# Rechargeable_battery_capacity_tester_v1a.net
KiCad netlist of a schematic drawn in EAGLE
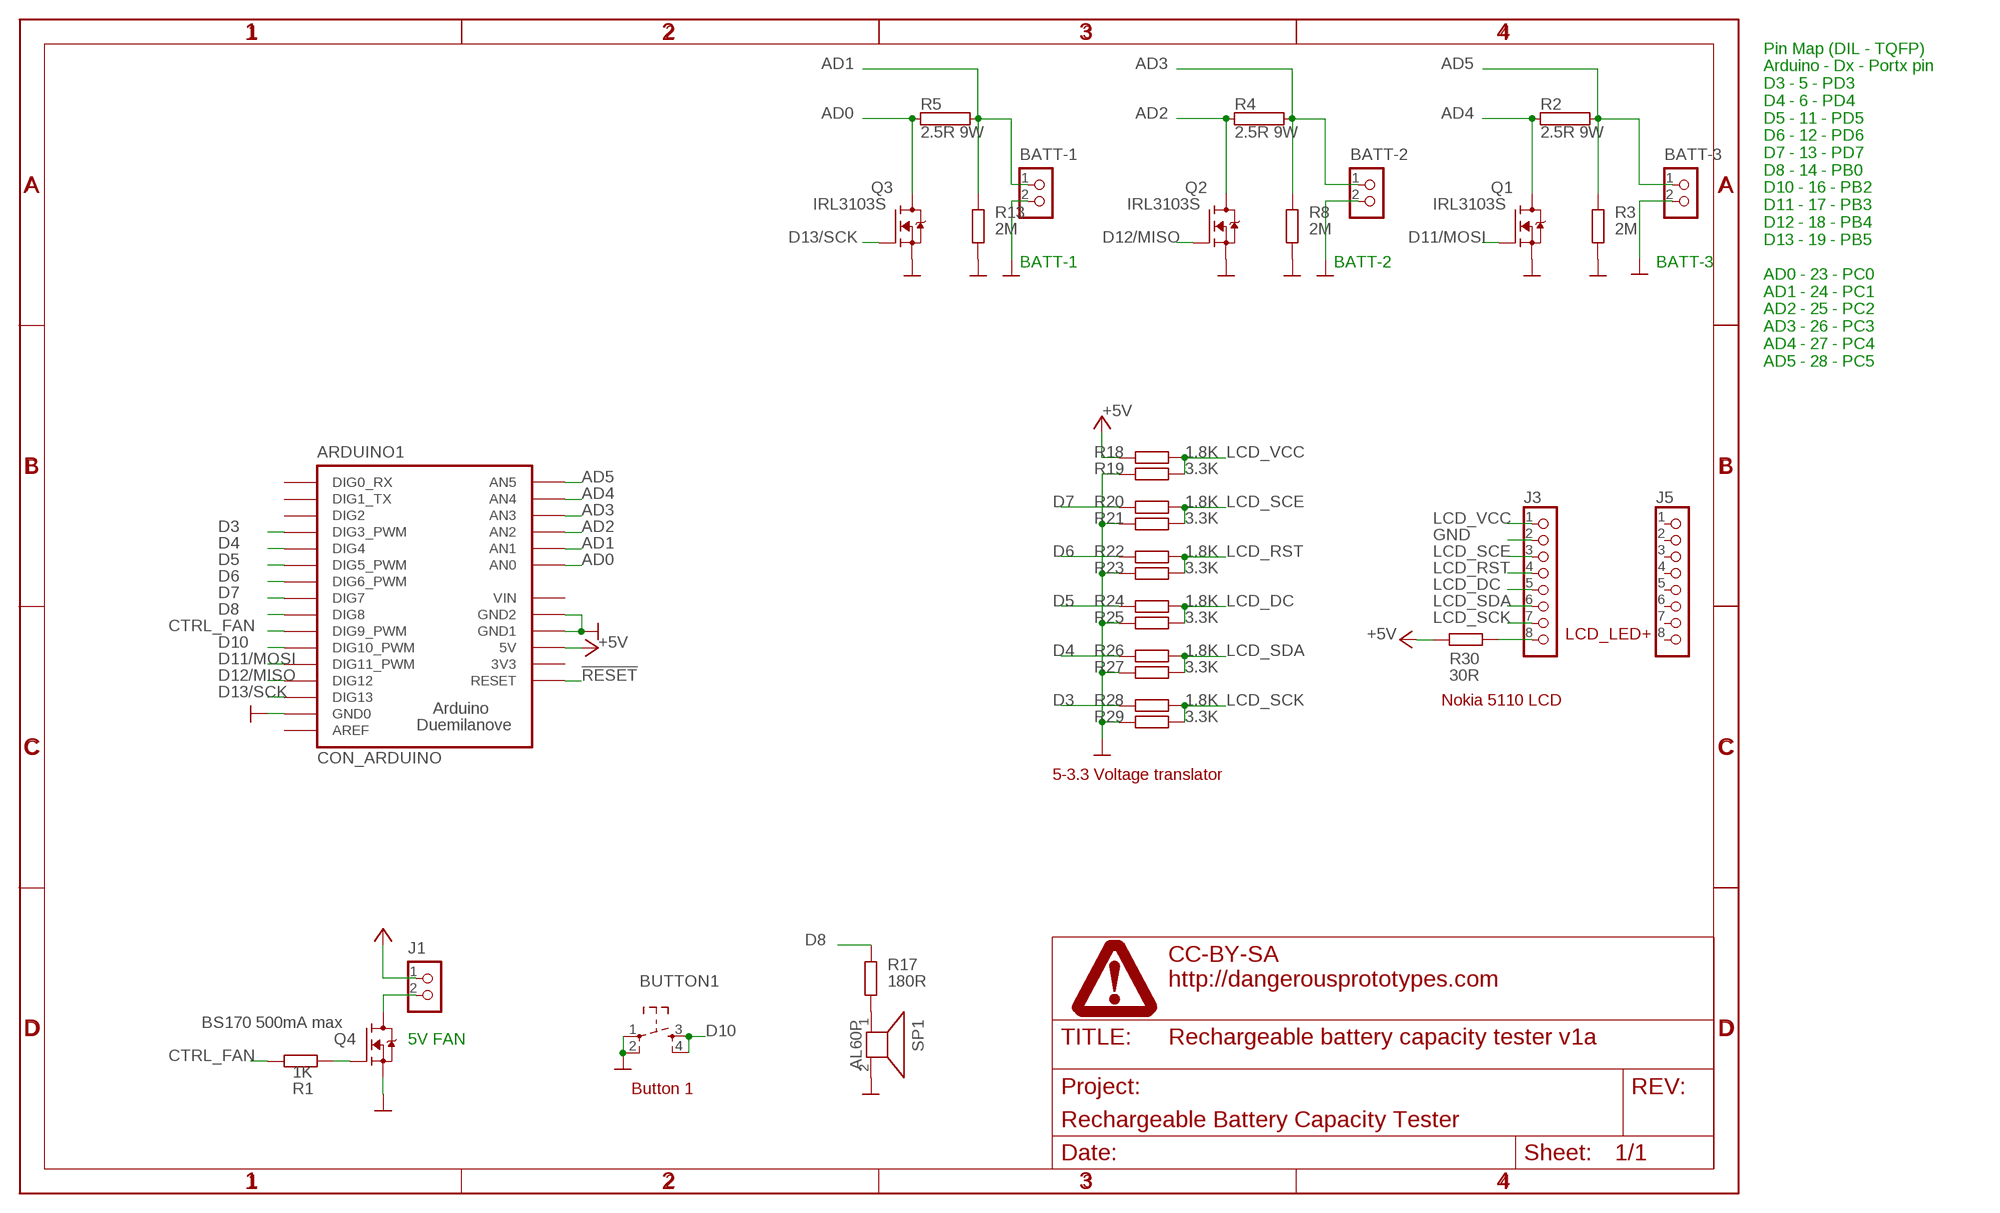
[diagram p0: schematic, sheet 1]

(export (version "E")
  (design (tool "Eeschema 10.0.6"))
  (components
    (comp (ref "ARDUINO1")
      (value "CON_ARDUINO")
      (footprint "eagle-import:CON_ARDUINO")
      (libsource (lib "eagle-import") (part "CON_ARDUINO"))
    )
    (comp (ref "BATT-1")
      (value "CON_TERMINAL_BLOCK_02-5MM")
      (footprint "eagle-import:TERMINAL_BLOCK_2P_5")
      (libsource (lib "eagle-import") (part "CON_TERMINAL_BLOCK_02-5MM"))
    )
    (comp (ref "BATT-2")
      (value "CON_TERMINAL_BLOCK_02-5MM")
      (footprint "eagle-import:TERMINAL_BLOCK_2P_5")
      (libsource (lib "eagle-import") (part "CON_TERMINAL_BLOCK_02-5MM"))
    )
    (comp (ref "BATT-3")
      (value "CON_TERMINAL_BLOCK_02-5MM")
      (footprint "eagle-import:TERMINAL_BLOCK_2P_5")
      (libsource (lib "eagle-import") (part "CON_TERMINAL_BLOCK_02-5MM"))
    )
    (comp (ref "BUTTON1")
      (value "SW_TACT_4P")
      (footprint "eagle-import:SW_TACT_SMALL")
      (libsource (lib "eagle-import") (part "SW_TACT_4P"))
    )
    (comp (ref "J1")
      (value "CON_JST_2PIN-PTH")
      (footprint "eagle-import:CON_JST_2PIN")
      (libsource (lib "eagle-import") (part "CON_JST_2PIN-PTH"))
    )
    (comp (ref "J3")
      (value "CON_HEADER_1X08-PTH")
      (footprint "eagle-import:M1X8")
      (libsource (lib "eagle-import") (part "CON_HEADER_1X08-PTH"))
    )
    (comp (ref "J5")
      (value "CON_HEADER_1X08-PTH")
      (footprint "eagle-import:M1X8")
      (libsource (lib "eagle-import") (part "CON_HEADER_1X08-PTH"))
    )
    (comp (ref "Q1")
      (value "IRL3103S")
      (footprint "eagle-import:D2PAK")
      (libsource (lib "eagle-import") (part "TRANSISTOR_MOSFET-N-D2PAK"))
    )
    (comp (ref "Q2")
      (value "IRL3103S")
      (footprint "eagle-import:D2PAK")
      (libsource (lib "eagle-import") (part "TRANSISTOR_MOSFET-N-D2PAK"))
    )
    (comp (ref "Q3")
      (value "IRL3103S")
      (footprint "eagle-import:D2PAK")
      (libsource (lib "eagle-import") (part "TRANSISTOR_MOSFET-N-D2PAK"))
    )
    (comp (ref "Q4")
      (value "BS170 500mA max")
      (footprint "eagle-import:SOT-23")
      (libsource (lib "eagle-import") (part "TRANSISTOR_FET_BS170-SOT-23"))
    )
    (comp (ref "R1")
      (value "1K")
      (footprint "eagle-import:R603")
      (libsource (lib "eagle-import") (part "RESISTOR-0603"))
    )
    (comp (ref "R2")
      (value "2.5R 9W")
      (footprint "eagle-import:KH214-8")
      (libsource (lib "eagle-import") (part "RKH214-8"))
    )
    (comp (ref "R3")
      (value "2M")
      (footprint "eagle-import:R603")
      (libsource (lib "eagle-import") (part "RESISTOR-0603"))
    )
    (comp (ref "R4")
      (value "2.5R 9W")
      (footprint "eagle-import:KH214-8")
      (libsource (lib "eagle-import") (part "RKH214-8"))
    )
    (comp (ref "R5")
      (value "2.5R 9W")
      (footprint "eagle-import:KH214-8")
      (libsource (lib "eagle-import") (part "RKH214-8"))
    )
    (comp (ref "R8")
      (value "2M")
      (footprint "eagle-import:R603")
      (libsource (lib "eagle-import") (part "RESISTOR-0603"))
    )
    (comp (ref "R13")
      (value "2M")
      (footprint "eagle-import:R603")
      (libsource (lib "eagle-import") (part "RESISTOR-0603"))
    )
    (comp (ref "R17")
      (value "180R")
      (footprint "eagle-import:R603")
      (libsource (lib "eagle-import") (part "RESISTOR-0603"))
    )
    (comp (ref "R18")
      (value "1.8K")
      (footprint "eagle-import:R603")
      (libsource (lib "eagle-import") (part "RESISTOR-0603"))
    )
    (comp (ref "R19")
      (value "3.3K")
      (footprint "eagle-import:R603")
      (libsource (lib "eagle-import") (part "RESISTOR-0603"))
    )
    (comp (ref "R20")
      (value "1.8K")
      (footprint "eagle-import:R603")
      (libsource (lib "eagle-import") (part "RESISTOR-0603"))
    )
    (comp (ref "R21")
      (value "3.3K")
      (footprint "eagle-import:R603")
      (libsource (lib "eagle-import") (part "RESISTOR-0603"))
    )
    (comp (ref "R22")
      (value "1.8K")
      (footprint "eagle-import:R603")
      (libsource (lib "eagle-import") (part "RESISTOR-0603"))
    )
    (comp (ref "R23")
      (value "3.3K")
      (footprint "eagle-import:R603")
      (libsource (lib "eagle-import") (part "RESISTOR-0603"))
    )
    (comp (ref "R24")
      (value "1.8K")
      (footprint "eagle-import:R603")
      (libsource (lib "eagle-import") (part "RESISTOR-0603"))
    )
    (comp (ref "R25")
      (value "3.3K")
      (footprint "eagle-import:R603")
      (libsource (lib "eagle-import") (part "RESISTOR-0603"))
    )
    (comp (ref "R26")
      (value "1.8K")
      (footprint "eagle-import:R603")
      (libsource (lib "eagle-import") (part "RESISTOR-0603"))
    )
    (comp (ref "R27")
      (value "3.3K")
      (footprint "eagle-import:R603")
      (libsource (lib "eagle-import") (part "RESISTOR-0603"))
    )
    (comp (ref "R28")
      (value "1.8K")
      (footprint "eagle-import:R603")
      (libsource (lib "eagle-import") (part "RESISTOR-0603"))
    )
    (comp (ref "R29")
      (value "3.3K")
      (footprint "eagle-import:R603")
      (libsource (lib "eagle-import") (part "RESISTOR-0603"))
    )
    (comp (ref "R30")
      (value "30R")
      (footprint "eagle-import:R603")
      (libsource (lib "eagle-import") (part "RESISTOR-0603"))
    )
    (comp (ref "SP1")
      (value "AL60P")
      (footprint "eagle-import:AL60P")
      (libsource (lib "eagle-import") (part "AL60P"))
    )
    (comp (ref "U$1")
      (value "FRAME_DINA4_L")
      (footprint "eagle-import:DP_LOGO")
      (fields
        (field (name "FF1") "Credits to: http://www.instructables.com/member/BrianH/")
        (field (name "PROJECT") "Rechargeable Battery Capacity Tester")
        (field (name "URL1") "http://dangerousprototypes.com")
        (field (name "URL2") "http://www.instructables.com/id/Rechargeable-Battery-Capacity-Tester/")
      )
      (libsource (lib "eagle-import") (part "FRAME_DINA4_L"))
    )
  )
  (nets
    (net (code "1") (name "/AD0") (class "Default")
      (node (ref "ARDUINO1") (pin "A_0") (pinfunction "AN0_A_0") (pintype "input"))
      (node (ref "Q3") (pin "2") (pinfunction "D_2") (pintype "passive"))
      (node (ref "R5") (pin "1") (pinfunction "1_1") (pintype "passive"))
    )
    (net (code "2") (name "/AD1") (class "Default")
      (node (ref "ARDUINO1") (pin "A_1") (pinfunction "AN1_A_1") (pintype "input"))
      (node (ref "BATT-1") (pin "1") (pinfunction "1_1") (pintype "passive"))
      (node (ref "R13") (pin "2") (pinfunction "2_2") (pintype "passive"))
      (node (ref "R5") (pin "2") (pinfunction "2_2") (pintype "passive"))
    )
    (net (code "3") (name "/AD2") (class "Default")
      (node (ref "ARDUINO1") (pin "A_2") (pinfunction "AN2_A_2") (pintype "input"))
      (node (ref "Q2") (pin "2") (pinfunction "D_2") (pintype "passive"))
      (node (ref "R4") (pin "1") (pinfunction "1_1") (pintype "passive"))
    )
    (net (code "4") (name "/AD3") (class "Default")
      (node (ref "ARDUINO1") (pin "A_3") (pinfunction "AN3_A_3") (pintype "input"))
      (node (ref "BATT-2") (pin "1") (pinfunction "1_1") (pintype "passive"))
      (node (ref "R4") (pin "2") (pinfunction "2_2") (pintype "passive"))
      (node (ref "R8") (pin "2") (pinfunction "2_2") (pintype "passive"))
    )
    (net (code "5") (name "/AD4") (class "Default")
      (node (ref "ARDUINO1") (pin "A_4") (pinfunction "AN4_A_4") (pintype "input"))
      (node (ref "Q1") (pin "2") (pinfunction "D_2") (pintype "passive"))
      (node (ref "R2") (pin "1") (pinfunction "1_1") (pintype "passive"))
    )
    (net (code "6") (name "/AD5") (class "Default")
      (node (ref "ARDUINO1") (pin "A_5") (pinfunction "AN5_A_5") (pintype "input"))
      (node (ref "BATT-3") (pin "1") (pinfunction "1_1") (pintype "passive"))
      (node (ref "R2") (pin "2") (pinfunction "2_2") (pintype "passive"))
      (node (ref "R3") (pin "2") (pinfunction "2_2") (pintype "passive"))
    )
    (net (code "7") (name "/CTRL_FAN") (class "Default")
      (node (ref "ARDUINO1") (pin "D_9") (pinfunction "DIG9_PWM_D_9") (pintype "bidirectional"))
      (node (ref "R1") (pin "1") (pinfunction "1_1") (pintype "passive"))
    )
    (net (code "8") (name "/D3") (class "Default")
      (node (ref "ARDUINO1") (pin "D_3") (pinfunction "DIG3_PWM_D_3") (pintype "bidirectional"))
      (node (ref "R28") (pin "1") (pinfunction "1_1") (pintype "passive"))
    )
    (net (code "9") (name "/D4") (class "Default")
      (node (ref "ARDUINO1") (pin "D_4") (pinfunction "DIG4_D_4") (pintype "bidirectional"))
      (node (ref "R26") (pin "1") (pinfunction "1_1") (pintype "passive"))
    )
    (net (code "10") (name "/D5") (class "Default")
      (node (ref "ARDUINO1") (pin "D_5") (pinfunction "DIG5_PWM_D_5") (pintype "bidirectional"))
      (node (ref "R24") (pin "1") (pinfunction "1_1") (pintype "passive"))
    )
    (net (code "11") (name "/D6") (class "Default")
      (node (ref "ARDUINO1") (pin "D_6") (pinfunction "DIG6_PWM_D_6") (pintype "bidirectional"))
      (node (ref "R22") (pin "1") (pinfunction "1_1") (pintype "passive"))
    )
    (net (code "12") (name "/D7") (class "Default")
      (node (ref "ARDUINO1") (pin "D_7") (pinfunction "DIG7_D_7") (pintype "bidirectional"))
      (node (ref "R20") (pin "1") (pinfunction "1_1") (pintype "passive"))
    )
    (net (code "13") (name "/D8") (class "Default")
      (node (ref "ARDUINO1") (pin "D_8") (pinfunction "DIG8_D_8") (pintype "bidirectional"))
      (node (ref "R17") (pin "2") (pinfunction "2_2") (pintype "passive"))
    )
    (net (code "14") (name "/D10") (class "Default")
      (node (ref "ARDUINO1") (pin "D_10") (pinfunction "DIG10_PWM_D_10") (pintype "bidirectional"))
      (node (ref "BUTTON1") (pin "3") (pinfunction "3_3") (pintype "passive"))
      (node (ref "BUTTON1") (pin "4") (pinfunction "4_4") (pintype "passive"))
    )
    (net (code "15") (name "/D11{slash}MOSI") (class "Default")
      (node (ref "ARDUINO1") (pin "D_11") (pinfunction "DIG11_PWM_D_11") (pintype "bidirectional"))
      (node (ref "Q1") (pin "1") (pinfunction "G_1") (pintype "passive"))
    )
    (net (code "16") (name "/D12{slash}MISO") (class "Default")
      (node (ref "ARDUINO1") (pin "D_12") (pinfunction "DIG12_D_12") (pintype "bidirectional"))
      (node (ref "Q2") (pin "1") (pinfunction "G_1") (pintype "passive"))
    )
    (net (code "17") (name "/D13{slash}SCK") (class "Default")
      (node (ref "ARDUINO1") (pin "D_13") (pinfunction "DIG13_D_13") (pintype "bidirectional"))
      (node (ref "Q3") (pin "1") (pinfunction "G_1") (pintype "passive"))
    )
    (net (code "18") (name "/LCD_DC") (class "Default")
      (node (ref "J3") (pin "5") (pinfunction "5_5") (pintype "passive"))
      (node (ref "R24") (pin "2") (pinfunction "2_2") (pintype "passive"))
      (node (ref "R25") (pin "2") (pinfunction "2_2") (pintype "passive"))
    )
    (net (code "19") (name "/LCD_RST") (class "Default")
      (node (ref "J3") (pin "4") (pinfunction "4_4") (pintype "passive"))
      (node (ref "R22") (pin "2") (pinfunction "2_2") (pintype "passive"))
      (node (ref "R23") (pin "2") (pinfunction "2_2") (pintype "passive"))
    )
    (net (code "20") (name "/LCD_SCE") (class "Default")
      (node (ref "J3") (pin "3") (pinfunction "3_3") (pintype "passive"))
      (node (ref "R20") (pin "2") (pinfunction "2_2") (pintype "passive"))
      (node (ref "R21") (pin "2") (pinfunction "2_2") (pintype "passive"))
    )
    (net (code "21") (name "/LCD_SCK") (class "Default")
      (node (ref "J3") (pin "7") (pinfunction "7_7") (pintype "passive"))
      (node (ref "R28") (pin "2") (pinfunction "2_2") (pintype "passive"))
      (node (ref "R29") (pin "2") (pinfunction "2_2") (pintype "passive"))
    )
    (net (code "22") (name "/LCD_SDA") (class "Default")
      (node (ref "J3") (pin "6") (pinfunction "6_6") (pintype "passive"))
      (node (ref "R26") (pin "2") (pinfunction "2_2") (pintype "passive"))
      (node (ref "R27") (pin "2") (pinfunction "2_2") (pintype "passive"))
    )
    (net (code "23") (name "/LCD_VCC") (class "Default")
      (node (ref "J3") (pin "1") (pinfunction "1_1") (pintype "passive"))
      (node (ref "R18") (pin "2") (pinfunction "2_2") (pintype "passive"))
      (node (ref "R19") (pin "2") (pinfunction "2_2") (pintype "passive"))
    )
    (net (code "24") (name "/VIN") (class "Default")
      (node (ref "ARDUINO1") (pin "VIN") (pinfunction "VIN_VIN") (pintype "power_in"))
    )
    (net (code "25") (name "/~{RESET}") (class "Default")
      (node (ref "ARDUINO1") (pin "RESET") (pinfunction "RESET_RESET") (pintype "input"))
    )
    (net (code "26") (name "Net-(J3-Pad8)") (class "Default")
      (node (ref "J3") (pin "8") (pinfunction "8_8") (pintype "passive"))
      (node (ref "R30") (pin "2") (pinfunction "2_2") (pintype "passive"))
    )
    (net (code "27") (name "Net-(Q4-D)") (class "Default")
      (node (ref "J1") (pin "2") (pinfunction "2_2") (pintype "passive"))
      (node (ref "Q4") (pin "3") (pinfunction "D_3") (pintype "passive"))
    )
    (net (code "28") (name "Net-(Q4-G)") (class "Default")
      (node (ref "Q4") (pin "1") (pinfunction "G_1") (pintype "passive"))
      (node (ref "R1") (pin "2") (pinfunction "2_2") (pintype "passive"))
    )
    (net (code "29") (name "Net-(R17-Pad1)") (class "Default")
      (node (ref "R17") (pin "1") (pinfunction "1_1") (pintype "passive"))
      (node (ref "SP1") (pin "1") (pinfunction "1_1") (pintype "passive"))
    )
    (net (code "30") (name "SUPPLY_+5V") (class "Default")
      (node (ref "ARDUINO1") (pin "5V") (pinfunction "5V_5V") (pintype "bidirectional"))
      (node (ref "J1") (pin "1") (pinfunction "1_1") (pintype "passive"))
      (node (ref "R18") (pin "1") (pinfunction "1_1") (pintype "passive"))
      (node (ref "R30") (pin "1") (pinfunction "1_1") (pintype "passive"))
    )
    (net (code "31") (name "SUPPLY_GND") (class "Default")
      (node (ref "ARDUINO1") (pin "GND0") (pinfunction "GND0_GND0") (pintype "power_in"))
      (node (ref "ARDUINO1") (pin "GND1") (pinfunction "GND1_GND1") (pintype "power_in"))
      (node (ref "ARDUINO1") (pin "GND2") (pinfunction "GND2_GND2") (pintype "power_in"))
      (node (ref "BATT-1") (pin "2") (pinfunction "2_2") (pintype "passive"))
      (node (ref "BATT-2") (pin "2") (pinfunction "2_2") (pintype "passive"))
      (node (ref "BATT-3") (pin "2") (pinfunction "2_2") (pintype "passive"))
      (node (ref "BUTTON1") (pin "1") (pinfunction "1_1") (pintype "passive"))
      (node (ref "BUTTON1") (pin "2") (pinfunction "2_2") (pintype "passive"))
      (node (ref "J3") (pin "2") (pinfunction "2_2") (pintype "passive"))
      (node (ref "Q1") (pin "3") (pinfunction "S_3") (pintype "passive"))
      (node (ref "Q2") (pin "3") (pinfunction "S_3") (pintype "passive"))
      (node (ref "Q3") (pin "3") (pinfunction "S_3") (pintype "passive"))
      (node (ref "Q4") (pin "2") (pinfunction "S_2") (pintype "passive"))
      (node (ref "R13") (pin "1") (pinfunction "1_1") (pintype "passive"))
      (node (ref "R19") (pin "1") (pinfunction "1_1") (pintype "passive"))
      (node (ref "R21") (pin "1") (pinfunction "1_1") (pintype "passive"))
      (node (ref "R23") (pin "1") (pinfunction "1_1") (pintype "passive"))
      (node (ref "R25") (pin "1") (pinfunction "1_1") (pintype "passive"))
      (node (ref "R27") (pin "1") (pinfunction "1_1") (pintype "passive"))
      (node (ref "R29") (pin "1") (pinfunction "1_1") (pintype "passive"))
      (node (ref "R3") (pin "1") (pinfunction "1_1") (pintype "passive"))
      (node (ref "R8") (pin "1") (pinfunction "1_1") (pintype "passive"))
      (node (ref "SP1") (pin "2") (pinfunction "2_2") (pintype "passive"))
    )
    (net (code "32") (name "unconnected-(ARDUINO1-DIG0_RX-PadD_0)") (class "Default")
      (node (ref "ARDUINO1") (pin "D_0") (pinfunction "DIG0_RX_D_0") (pintype "bidirectional"))
    )
    (net (code "33") (name "unconnected-(ARDUINO1-DIG1_TX-PadD_1)") (class "Default")
      (node (ref "ARDUINO1") (pin "D_1") (pinfunction "DIG1_TX_D_1") (pintype "bidirectional"))
    )
    (net (code "34") (name "unconnected-(ARDUINO1-DIG2-PadD_2)") (class "Default")
      (node (ref "ARDUINO1") (pin "D_2") (pinfunction "DIG2_D_2") (pintype "bidirectional"))
    )
    (net (code "35") (name "unconnected-(ARDUINO1-Pad3V3)") (class "Default")
      (node (ref "ARDUINO1") (pin "3V3") (pinfunction "3V3_3V3") (pintype "bidirectional"))
    )
    (net (code "36") (name "unconnected-(ARDUINO1-PadAREF)") (class "Default")
      (node (ref "ARDUINO1") (pin "AREF") (pinfunction "AREF_AREF") (pintype "bidirectional"))
    )
    (net (code "37") (name "unconnected-(J5-Pad1)") (class "Default")
      (node (ref "J5") (pin "1") (pinfunction "1_1") (pintype "passive"))
    )
    (net (code "38") (name "unconnected-(J5-Pad2)") (class "Default")
      (node (ref "J5") (pin "2") (pinfunction "2_2") (pintype "passive"))
    )
    (net (code "39") (name "unconnected-(J5-Pad3)") (class "Default")
      (node (ref "J5") (pin "3") (pinfunction "3_3") (pintype "passive"))
    )
    (net (code "40") (name "unconnected-(J5-Pad4)") (class "Default")
      (node (ref "J5") (pin "4") (pinfunction "4_4") (pintype "passive"))
    )
    (net (code "41") (name "unconnected-(J5-Pad5)") (class "Default")
      (node (ref "J5") (pin "5") (pinfunction "5_5") (pintype "passive"))
    )
    (net (code "42") (name "unconnected-(J5-Pad6)") (class "Default")
      (node (ref "J5") (pin "6") (pinfunction "6_6") (pintype "passive"))
    )
    (net (code "43") (name "unconnected-(J5-Pad7)") (class "Default")
      (node (ref "J5") (pin "7") (pinfunction "7_7") (pintype "passive"))
    )
    (net (code "44") (name "unconnected-(J5-Pad8)") (class "Default")
      (node (ref "J5") (pin "8") (pinfunction "8_8") (pintype "passive"))
    )
  )
)
